# BT612-4.net
KiCad netlist of a schematic drawn in Altium Designer
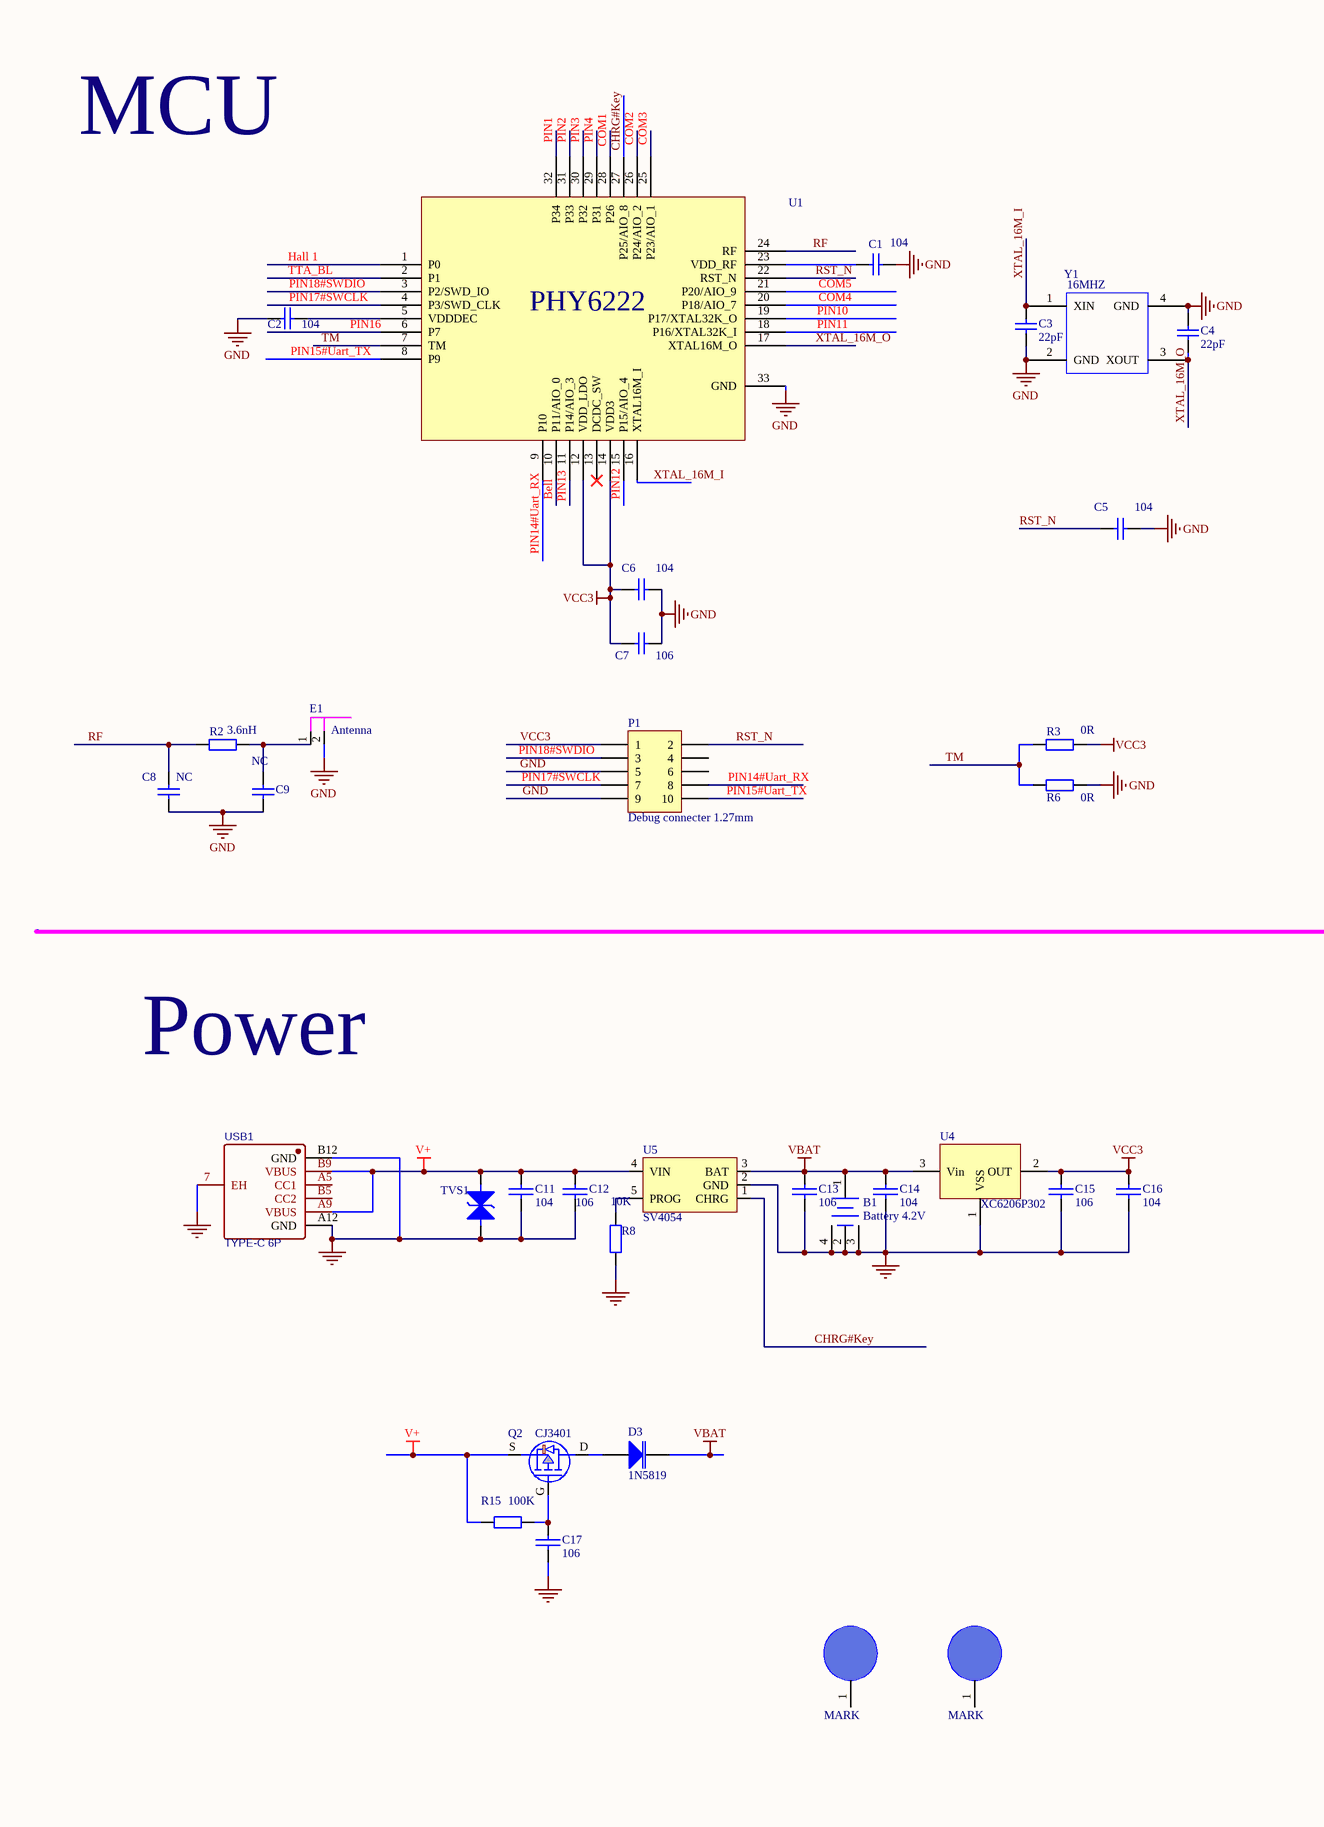
[diagram p0: BT612-4.SchDoc, left]
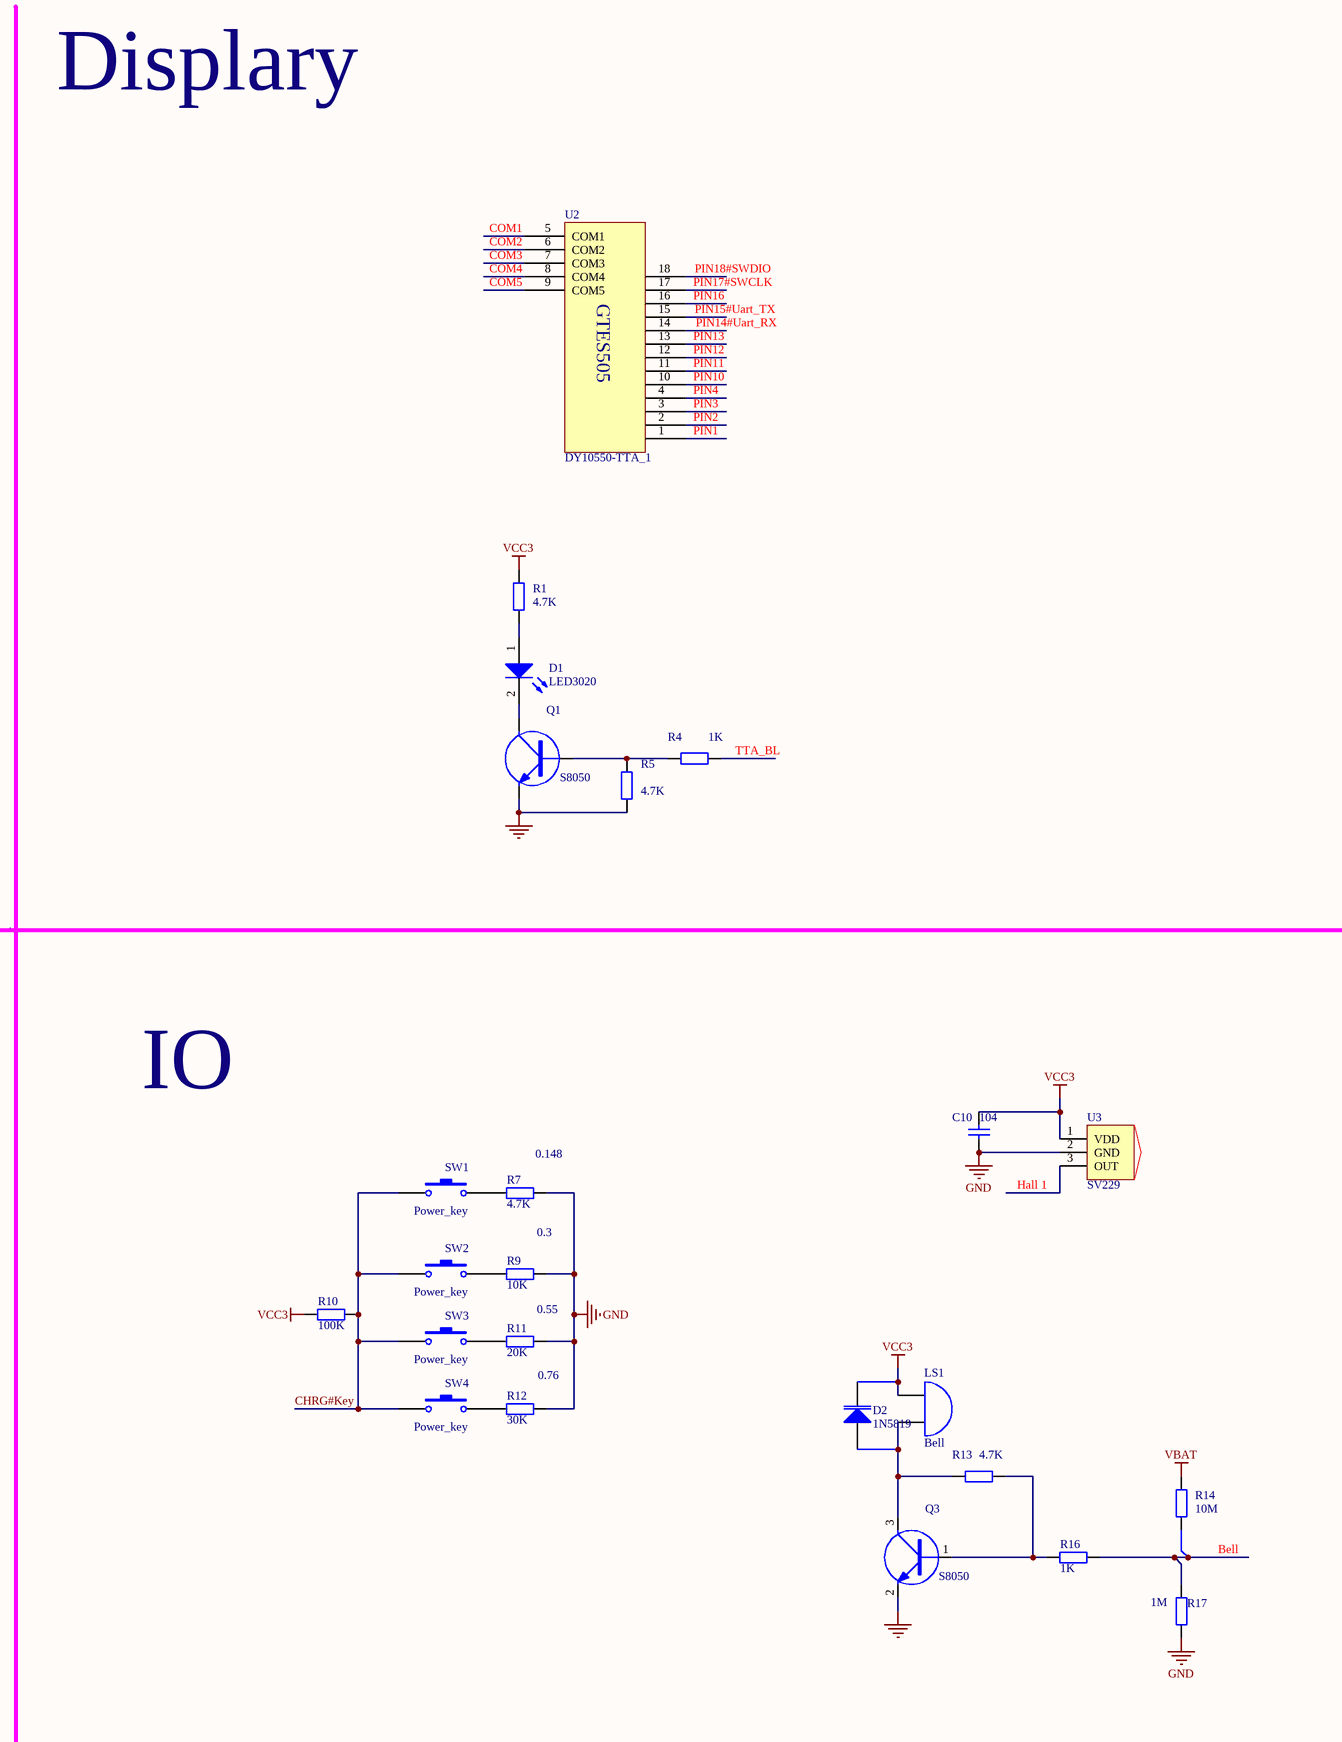
[diagram p1: BT612-4.SchDoc, right]

(export (version "E")
  (design (tool "Eeschema 10.0.6"))
  (components
    (comp (ref "B1")
      (value "Battery 4.2V")
      (footprint "BAT2P-1.25")
      (description "Multicell Battery")
      (fields (field (name "PUBLISHER") "Altium Limited"))
      (libsource (lib "SR4K_PHY6222_simplify_v1") (part "Battery"))
    )
    (comp (ref "C1")
      (value "104")
      (footprint "0402C")
      (description "Capacitor")
      (fields (field (name "PUBLISHER") "Altium Limited"))
      (libsource (lib "Miscellaneous Devices") (part "Cap"))
    )
    (comp (ref "C2")
      (value "104")
      (footprint "0402C")
      (description "Capacitor")
      (fields (field (name "PUBLISHER") "Altium Limited"))
      (libsource (lib "Miscellaneous Devices") (part "Cap"))
    )
    (comp (ref "C3")
      (value "22pF")
      (footprint "0402C")
      (description "Capacitor")
      (fields (field (name "PUBLISHER") "Altium Limited"))
      (libsource (lib "Miscellaneous Devices") (part "Cap"))
    )
    (comp (ref "C4")
      (value "22pF")
      (footprint "0402C")
      (description "Capacitor")
      (libsource (lib "Miscellaneous Devices") (part "Cap"))
    )
    (comp (ref "C5")
      (value "104")
      (footprint "0402C")
      (description "Capacitor")
      (fields (field (name "PUBLISHER") "Altium Limited"))
      (libsource (lib "Miscellaneous Devices") (part "Cap"))
    )
    (comp (ref "C6")
      (value "104")
      (footprint "0402C")
      (description "Capacitor")
      (fields (field (name "PUBLISHER") "Altium Limited"))
      (libsource (lib "Miscellaneous Devices") (part "Cap"))
    )
    (comp (ref "C7")
      (value "106")
      (footprint "0603-C")
      (description "Capacitor")
      (fields (field (name "PUBLISHER") "Altium Limited"))
      (libsource (lib "Miscellaneous Devices") (part "Cap"))
    )
    (comp (ref "C8")
      (value "NC")
      (footprint "0402C")
      (description "Capacitor")
      (fields (field (name "PUBLISHER") "Altium Limited"))
      (libsource (lib "Miscellaneous Devices") (part "Cap"))
    )
    (comp (ref "C9")
      (value "NC")
      (footprint "0402C")
      (description "Capacitor")
      (fields (field (name "PUBLISHER") "Altium Limited"))
      (libsource (lib "Miscellaneous Devices") (part "Cap"))
    )
    (comp (ref "C10")
      (value "104")
      (footprint "0402C")
      (description "Capacitor")
      (fields (field (name "PUBLISHER") "Altium Limited"))
      (libsource (lib "Miscellaneous Devices") (part "Cap"))
    )
    (comp (ref "C11")
      (value "104")
      (footprint "0402C")
      (description "Capacitor")
      (libsource (lib "*") (part "CAP"))
    )
    (comp (ref "C12")
      (value "106")
      (footprint "0603-C")
      (description "Capacitor")
      (libsource (lib "*") (part "CAP"))
    )
    (comp (ref "C13")
      (value "106")
      (footprint "0603-C")
      (description "Capacitor")
      (libsource (lib "*") (part "CAP"))
    )
    (comp (ref "C14")
      (value "104")
      (footprint "0402C")
      (description "Capacitor")
      (libsource (lib "*") (part "CAP"))
    )
    (comp (ref "C15")
      (value "106")
      (footprint "0603-C")
      (description "Capacitor")
      (libsource (lib "*") (part "CAP"))
    )
    (comp (ref "C16")
      (value "104")
      (footprint "0402C")
      (description "Capacitor")
      (libsource (lib "*") (part "CAP"))
    )
    (comp (ref "C17")
      (value "106")
      (footprint "0603-C")
      (description "Capacitor")
      (libsource (lib "*") (part "CAP"))
    )
    (comp (ref "D1")
      (value "LED3020")
      (footprint "LED-3020")
      (description "Typical INFRARED GaAs LED")
      (fields (field (name "PUBLISHER") "Altium Limited"))
      (libsource (lib "Miscellaneous Devices") (part "LED0"))
    )
    (comp (ref "D2")
      (value "1N5819")
      (footprint "SOD323")
      (description "Variable Capacitance Diode")
      (fields (field (name "PUBLISHER") "Altium Limited"))
      (libsource (lib "Miscellaneous Devices") (part "D Varactor"))
    )
    (comp (ref "D3")
      (value "1N5819")
      (footprint "SOD323")
      (description "Variable Capacitance Diode")
      (fields (field (name "PUBLISHER") "Altium Limited"))
      (libsource (lib "Miscellaneous Devices") (part "D Varactor"))
    )
    (comp (ref "E1") (value "Antenna") (footprint "BT-ANT") (libsource (lib "Schlib") (part "Antenna")))
    (comp (ref "LS1")
      (value "Bell")
      (footprint "BUZZ-12085")
      (description "Electrical Bell")
      (fields (field (name "PUBLISHER") "Altium Limited"))
      (libsource (lib "Miscellaneous Devices") (part "Bell"))
    )
    (comp (ref "P1")
      (value "Debug connecter 1.27mm")
      (footprint "SIP5-X2-1.27")
      (description "Header, 5-Pin, Dual row")
      (fields (field (name "PUBLISHER") "Altium Limited"))
      (libsource (lib "Miscellaneous Connectors") (part "Header 5X2"))
    )
    (comp (ref "Q1")
      (value "S8050")
      (footprint "SOT23")
      (description "NPN Transistor")
      (libsource (lib "*") (part "NPN"))
    )
    (comp (ref "Q2") (value "CJ3401") (footprint "SOT-23-GSD") (libsource (lib "*") (part "P-MOS")))
    (comp (ref "Q3")
      (value "S8050")
      (footprint "SOT23")
      (description "NPN Transistor")
      (libsource (lib "") (part "NPN_1"))
    )
    (comp (ref "R1")
      (value "4.7K")
      (footprint "0402R")
      (description "Resistor")
      (fields (field (name "PUBLISHER") "Altium Limited"))
      (libsource (lib "") (part "Res2_2"))
    )
    (comp (ref "R2")
      (value "3.6nH")
      (footprint "0402R")
      (description "Resistor")
      (fields (field (name "PUBLISHER") "Altium Limited"))
      (libsource (lib "") (part "Res2_1"))
    )
    (comp (ref "R3")
      (value "0R")
      (footprint "0402R")
      (description "Resistor")
      (fields (field (name "PUBLISHER") "Altium Limited"))
      (libsource (lib "") (part "Res2_1"))
    )
    (comp (ref "R4")
      (value "1K")
      (footprint "0402R")
      (description "Resistor")
      (fields (field (name "PUBLISHER") "Altium Limited"))
      (libsource (lib "Miscellaneous Devices") (part "Res2"))
    )
    (comp (ref "R5")
      (value "4.7K")
      (footprint "0402R")
      (description "Resistor")
      (fields (field (name "PUBLISHER") "Altium Limited"))
      (libsource (lib "") (part "Res2_2"))
    )
    (comp (ref "R6")
      (value "0R")
      (footprint "0402R")
      (description "Resistor")
      (fields (field (name "PUBLISHER") "Altium Limited"))
      (libsource (lib "") (part "Res2_1"))
    )
    (comp (ref "R7")
      (value "4.7K")
      (footprint "0402R")
      (description "Resistor")
      (fields (field (name "PUBLISHER") "Altium Limited"))
      (libsource (lib "Miscellaneous Devices") (part "Res2"))
    )
    (comp (ref "R8")
      (value "10K")
      (footprint "0402R")
      (description "1%@100mA")
      (fields (field (name "PUBLISHER") "Altium Limited"))
      (libsource (lib "") (part "Res2_2"))
    )
    (comp (ref "R9")
      (value "10K")
      (footprint "0402R")
      (description "Resistor")
      (fields (field (name "PUBLISHER") "Altium Limited"))
      (libsource (lib "Miscellaneous Devices") (part "Res2"))
    )
    (comp (ref "R10")
      (value "100K")
      (footprint "0402R")
      (description "Resistor")
      (fields (field (name "PUBLISHER") "Altium Limited"))
      (libsource (lib "Miscellaneous Devices") (part "Res2"))
    )
    (comp (ref "R11")
      (value "20K")
      (footprint "0402R")
      (description "Resistor")
      (fields (field (name "PUBLISHER") "Altium Limited"))
      (libsource (lib "Miscellaneous Devices") (part "Res2"))
    )
    (comp (ref "R12")
      (value "30K")
      (footprint "0402R")
      (description "Resistor")
      (fields (field (name "PUBLISHER") "Altium Limited"))
      (libsource (lib "Miscellaneous Devices") (part "Res2"))
    )
    (comp (ref "R13")
      (value "4.7K")
      (footprint "0402R")
      (description "Resistor")
      (fields (field (name "PUBLISHER") "Altium Limited"))
      (libsource (lib "") (part "Res2_1"))
    )
    (comp (ref "R14")
      (value "10M")
      (footprint "0402R")
      (description "Resistor")
      (fields (field (name "PUBLISHER") "Altium Limited"))
      (libsource (lib "") (part "Res2_2"))
    )
    (comp (ref "R15")
      (value "100K")
      (footprint "0402R")
      (description "1%@100mA")
      (fields (field (name "PUBLISHER") "Altium Limited"))
      (libsource (lib "") (part "Res2_1"))
    )
    (comp (ref "R16")
      (value "1K")
      (footprint "0402R")
      (description "Resistor")
      (fields (field (name "PUBLISHER") "Altium Limited"))
      (libsource (lib "Miscellaneous Devices") (part "Res2"))
    )
    (comp (ref "R17")
      (value "1M")
      (footprint "0402R")
      (description "Resistor")
      (fields (field (name "PUBLISHER") "Altium Limited"))
      (libsource (lib "") (part "Res2_2"))
    )
    (comp (ref "SW1")
      (value "Power_key")
      (footprint "SW_PB_SMD_4X4")
      (description "Switch")
      (fields (field (name "PUBLISHER") "Altium Limited"))
      (libsource (lib "Miscellaneous Devices") (part "SW-PB"))
    )
    (comp (ref "SW2")
      (value "Power_key")
      (footprint "SW_PB_SMD_4X4")
      (description "Switch")
      (fields (field (name "PUBLISHER") "Altium Limited"))
      (libsource (lib "Miscellaneous Devices") (part "SW-PB"))
    )
    (comp (ref "SW3")
      (value "Power_key")
      (footprint "SW_PB_SMD_4X4")
      (description "Switch")
      (fields (field (name "PUBLISHER") "Altium Limited"))
      (libsource (lib "Miscellaneous Devices") (part "SW-PB"))
    )
    (comp (ref "SW4")
      (value "Power_key")
      (footprint "SW_PB_SMD_4X4")
      (description "Switch")
      (fields (field (name "PUBLISHER") "Altium Limited"))
      (libsource (lib "Miscellaneous Devices") (part "SW-PB"))
    )
    (comp (ref "TP1") (value "MARK") (footprint "MARK") (libsource (lib "BT612-4") (part "TP")))
    (comp (ref "TP2") (value "MARK") (footprint "MARK") (libsource (lib "BT612-4") (part "TP")))
    (comp (ref "TVS1") (value "TVS") (footprint "SOD323") (libsource (lib "*") (part "TVS")))
    (comp (ref "U1")
      (value "PHY6222")
      (footprint "QFN32-4*4")
      (libsource (lib "SR4K_PHY6222_simplify_v1") (part "PHY6222"))
    )
    (comp (ref "U2")
      (value "DY10550-TTA_1")
      (footprint "GTES505液晶屏")
      (libsource (lib "BT612-4") (part "DY10550-TTA_1"))
    )
    (comp (ref "U3") (value "SV229") (footprint "SOT23-3") (libsource (lib "*") (part "霍尔44E 938")))
    (comp (ref "U4") (value "XC6206P302") (footprint "SOT23") (libsource (lib "*") (part "XC6206P302")))
    (comp (ref "U5") (value "SV4054") (footprint "SOT23-5") (libsource (lib "*") (part "SV4054")))
    (comp (ref "USB1")
      (value "TYPE-C 6P")
      (footprint "TYPE-C 6P")
      (fields (field (name "BOM_SUPPLIER PART") "C456012") (field (name "CONTRIBUTOR") "LCSC"))
      (libsource (lib "altium-import") (part "root_0_mirrored_TYPE-C 6P_"))
    )
    (comp (ref "Y1") (value "16MHZ") (footprint "JZ-3225") (libsource (lib "*") (part "X1_1")))
  )
  (nets
    (net (code "1") (name "/Bell") (class "Default")
      (node (ref "R14") (pin "1") (pinfunction "1_1") (pintype "passive"))
      (node (ref "R16") (pin "2") (pinfunction "2_2") (pintype "passive"))
      (node (ref "R17") (pin "2") (pinfunction "2_2") (pintype "passive"))
      (node (ref "U1") (pin "10") (pinfunction "P11/AIO_0_10") (pintype "passive"))
    )
    (net (code "2") (name "/CHRG#Key") (class "Default")
      (node (ref "R10") (pin "2") (pinfunction "2_2") (pintype "passive"))
      (node (ref "SW1") (pin "1") (pinfunction "1_1") (pintype "passive"))
      (node (ref "SW2") (pin "1") (pinfunction "1_1") (pintype "passive"))
      (node (ref "SW3") (pin "1") (pinfunction "1_1") (pintype "passive"))
      (node (ref "SW4") (pin "1") (pinfunction "1_1") (pintype "passive"))
      (node (ref "U1") (pin "27") (pinfunction "P25/AIO_8_27") (pintype "passive"))
      (node (ref "U5") (pin "1") (pinfunction "CHRG_1") (pintype "passive"))
    )
    (net (code "3") (name "/COM1") (class "Default")
      (node (ref "U1") (pin "28") (pinfunction "P26_28") (pintype "passive"))
      (node (ref "U2") (pin "5") (pinfunction "COM1_5") (pintype "passive"))
    )
    (net (code "4") (name "/COM2") (class "Default")
      (node (ref "U1") (pin "26") (pinfunction "P24/AIO_2_26") (pintype "passive"))
      (node (ref "U2") (pin "6") (pinfunction "COM2_6") (pintype "passive"))
    )
    (net (code "5") (name "/COM3") (class "Default")
      (node (ref "U1") (pin "25") (pinfunction "P23/AIO_1_25") (pintype "passive"))
      (node (ref "U2") (pin "7") (pinfunction "COM3_7") (pintype "passive"))
    )
    (net (code "6") (name "/COM4") (class "Default")
      (node (ref "U1") (pin "20") (pinfunction "P18/AIO_7_20") (pintype "passive"))
      (node (ref "U2") (pin "8") (pinfunction "COM4_8") (pintype "passive"))
    )
    (net (code "7") (name "/COM5") (class "Default")
      (node (ref "U1") (pin "21") (pinfunction "P20/AIO_9_21") (pintype "passive"))
      (node (ref "U2") (pin "9") (pinfunction "COM5_9") (pintype "passive"))
    )
    (net (code "8") (name "/Hall 1") (class "Default")
      (node (ref "U1") (pin "1") (pinfunction "P0_1") (pintype "passive"))
      (node (ref "U3") (pin "3") (pinfunction "OUT_3") (pintype "passive"))
    )
    (net (code "9") (name "/PIN1") (class "Default")
      (node (ref "U1") (pin "32") (pinfunction "P34_32") (pintype "passive"))
      (node (ref "U2") (pin "1") (pintype "passive"))
    )
    (net (code "10") (name "/PIN2") (class "Default")
      (node (ref "U1") (pin "31") (pinfunction "P33_31") (pintype "passive"))
      (node (ref "U2") (pin "2") (pintype "passive"))
    )
    (net (code "11") (name "/PIN3") (class "Default")
      (node (ref "U1") (pin "30") (pinfunction "P32_30") (pintype "passive"))
      (node (ref "U2") (pin "3") (pintype "passive"))
    )
    (net (code "12") (name "/PIN4") (class "Default")
      (node (ref "U1") (pin "29") (pinfunction "P31_29") (pintype "passive"))
      (node (ref "U2") (pin "4") (pintype "passive"))
    )
    (net (code "13") (name "/PIN10") (class "Default")
      (node (ref "U1") (pin "19") (pinfunction "P17/XTAL32K_O_19") (pintype "passive"))
      (node (ref "U2") (pin "10") (pintype "passive"))
    )
    (net (code "14") (name "/PIN11") (class "Default")
      (node (ref "U1") (pin "18") (pinfunction "P16/XTAL32K_I_18") (pintype "passive"))
      (node (ref "U2") (pin "11") (pintype "passive"))
    )
    (net (code "15") (name "/PIN12") (class "Default")
      (node (ref "U1") (pin "15") (pinfunction "P15/AIO_4_15") (pintype "passive"))
      (node (ref "U2") (pin "12") (pintype "passive"))
    )
    (net (code "16") (name "/PIN13") (class "Default")
      (node (ref "U1") (pin "11") (pinfunction "P14/AIO_3_11") (pintype "passive"))
      (node (ref "U2") (pin "13") (pintype "passive"))
    )
    (net (code "17") (name "/PIN14#Uart_RX") (class "Default")
      (node (ref "P1") (pin "8") (pinfunction "8_8") (pintype "passive"))
      (node (ref "U1") (pin "9") (pinfunction "P10_9") (pintype "passive"))
      (node (ref "U2") (pin "14") (pintype "passive"))
    )
    (net (code "18") (name "/PIN15#Uart_TX") (class "Default")
      (node (ref "P1") (pin "10") (pinfunction "10_10") (pintype "passive"))
      (node (ref "U1") (pin "8") (pinfunction "P9_8") (pintype "passive"))
      (node (ref "U2") (pin "15") (pintype "passive"))
    )
    (net (code "19") (name "/PIN16") (class "Default")
      (node (ref "U1") (pin "6") (pinfunction "P7_6") (pintype "passive"))
      (node (ref "U2") (pin "16") (pintype "passive"))
    )
    (net (code "20") (name "/PIN17#SWCLK") (class "Default")
      (node (ref "P1") (pin "7") (pinfunction "7_7") (pintype "passive"))
      (node (ref "U1") (pin "4") (pinfunction "P3/SWD_CLK_4") (pintype "passive"))
      (node (ref "U2") (pin "17") (pintype "passive"))
    )
    (net (code "21") (name "/PIN18#SWDIO") (class "Default")
      (node (ref "P1") (pin "3") (pinfunction "3_3") (pintype "passive"))
      (node (ref "U1") (pin "3") (pinfunction "P2/SWD_IO_3") (pintype "passive"))
      (node (ref "U2") (pin "18") (pintype "passive"))
    )
    (net (code "22") (name "/RF") (class "Default")
      (node (ref "C8") (pin "1") (pinfunction "1_1") (pintype "passive"))
      (node (ref "R2") (pin "2") (pinfunction "2_2") (pintype "passive"))
      (node (ref "U1") (pin "24") (pinfunction "RF_24") (pintype "passive"))
    )
    (net (code "23") (name "/RST_N") (class "Default")
      (node (ref "C5") (pin "1") (pinfunction "1_1") (pintype "passive"))
      (node (ref "P1") (pin "2") (pinfunction "2_2") (pintype "passive"))
      (node (ref "U1") (pin "22") (pinfunction "RST_N_22") (pintype "passive"))
    )
    (net (code "24") (name "/TM") (class "Default")
      (node (ref "R3") (pin "2") (pinfunction "2_2") (pintype "passive"))
      (node (ref "R6") (pin "2") (pinfunction "2_2") (pintype "passive"))
      (node (ref "U1") (pin "7") (pinfunction "TM_7") (pintype "passive"))
    )
    (net (code "25") (name "/TTA_BL") (class "Default")
      (node (ref "R4") (pin "2") (pinfunction "2_2") (pintype "passive"))
      (node (ref "U1") (pin "2") (pinfunction "P1_2") (pintype "passive"))
    )
    (net (code "26") (name "/XTAL_16M_I") (class "Default")
      (node (ref "C3") (pin "1") (pinfunction "1_1") (pintype "passive"))
      (node (ref "U1") (pin "16") (pinfunction "XTAL16M_I_16") (pintype "passive"))
      (node (ref "Y1") (pin "1") (pinfunction "XIN_1") (pintype "passive"))
    )
    (net (code "27") (name "/XTAL_16M_O") (class "Default")
      (node (ref "C4") (pin "2") (pinfunction "2_2") (pintype "passive"))
      (node (ref "U1") (pin "17") (pinfunction "XTAL16M_O_17") (pintype "passive"))
      (node (ref "Y1") (pin "3") (pinfunction "XOUT_3") (pintype "passive"))
    )
    (net (code "28") (name "GND") (class "Default")
      (node (ref "B1") (pin "2") (pinfunction "-_2") (pintype "passive"))
      (node (ref "B1") (pin "3") (pinfunction "3_3") (pintype "passive"))
      (node (ref "B1") (pin "4") (pinfunction "4_4") (pintype "passive"))
      (node (ref "C1") (pin "2") (pinfunction "2_2") (pintype "passive"))
      (node (ref "C10") (pin "2") (pinfunction "2_2") (pintype "passive"))
      (node (ref "C11") (pin "1") (pinfunction "1_1") (pintype "passive"))
      (node (ref "C12") (pin "1") (pinfunction "1_1") (pintype "passive"))
      (node (ref "C13") (pin "1") (pinfunction "1_1") (pintype "passive"))
      (node (ref "C14") (pin "1") (pinfunction "1_1") (pintype "passive"))
      (node (ref "C15") (pin "1") (pinfunction "1_1") (pintype "passive"))
      (node (ref "C16") (pin "1") (pinfunction "1_1") (pintype "passive"))
      (node (ref "C17") (pin "1") (pinfunction "1_1") (pintype "passive"))
      (node (ref "C2") (pin "1") (pinfunction "1_1") (pintype "passive"))
      (node (ref "C3") (pin "2") (pinfunction "2_2") (pintype "passive"))
      (node (ref "C4") (pin "1") (pinfunction "1_1") (pintype "passive"))
      (node (ref "C5") (pin "2") (pinfunction "2_2") (pintype "passive"))
      (node (ref "C6") (pin "2") (pinfunction "2_2") (pintype "passive"))
      (node (ref "C7") (pin "2") (pinfunction "2_2") (pintype "passive"))
      (node (ref "C8") (pin "2") (pinfunction "2_2") (pintype "passive"))
      (node (ref "C9") (pin "2") (pinfunction "2_2") (pintype "passive"))
      (node (ref "E1") (pin "2") (pinfunction "2_2") (pintype "passive"))
      (node (ref "P1") (pin "5") (pinfunction "5_5") (pintype "passive"))
      (node (ref "P1") (pin "9") (pinfunction "9_9") (pintype "passive"))
      (node (ref "Q1") (pin "2") (pinfunction "E_2") (pintype "passive"))
      (node (ref "Q3") (pin "2") (pinfunction "E_2") (pintype "passive"))
      (node (ref "R11") (pin "2") (pinfunction "2_2") (pintype "passive"))
      (node (ref "R12") (pin "2") (pinfunction "2_2") (pintype "passive"))
      (node (ref "R17") (pin "1") (pinfunction "1_1") (pintype "passive"))
      (node (ref "R5") (pin "1") (pinfunction "1_1") (pintype "passive"))
      (node (ref "R6") (pin "1") (pinfunction "1_1") (pintype "passive"))
      (node (ref "R7") (pin "2") (pinfunction "2_2") (pintype "passive"))
      (node (ref "R8") (pin "1") (pinfunction "1_1") (pintype "passive"))
      (node (ref "R9") (pin "2") (pinfunction "2_2") (pintype "passive"))
      (node (ref "TVS1") (pin "1") (pinfunction "1_1") (pintype "passive"))
      (node (ref "U1") (pin "33") (pinfunction "GND_33") (pintype "power_in"))
      (node (ref "U3") (pin "2") (pinfunction "GND_2") (pintype "passive"))
      (node (ref "U4") (pin "1") (pinfunction "VSS_1") (pintype "passive"))
      (node (ref "U5") (pin "2") (pinfunction "GND_2") (pintype "passive"))
      (node (ref "USB1") (pin "7") (pinfunction "EH_7") (pintype "passive"))
      (node (ref "USB1") (pin "A12") (pinfunction "GND_A12") (pintype "passive"))
      (node (ref "USB1") (pin "B12") (pinfunction "GND_B12") (pintype "passive"))
      (node (ref "Y1") (pin "2") (pinfunction "GND_2") (pintype "power_in"))
      (node (ref "Y1") (pin "4") (pinfunction "GND_4") (pintype "power_in"))
    )
    (net (code "29") (name "Net-(C9-Pad1)") (class "Default")
      (node (ref "C9") (pin "1") (pinfunction "1_1") (pintype "passive"))
      (node (ref "E1") (pin "1") (pinfunction "1_1") (pintype "passive"))
      (node (ref "R2") (pin "1") (pinfunction "1_1") (pintype "passive"))
    )
    (net (code "30") (name "Net-(D1-A)") (class "Default")
      (node (ref "D1") (pin "1") (pinfunction "A_1") (pintype "passive"))
      (node (ref "R1") (pin "1") (pinfunction "1_1") (pintype "passive"))
    )
    (net (code "31") (name "Net-(D1-K)") (class "Default")
      (node (ref "D1") (pin "2") (pinfunction "K_2") (pintype "passive"))
      (node (ref "Q1") (pin "3") (pinfunction "C_3") (pintype "passive"))
    )
    (net (code "32") (name "Net-(LS1-B)") (class "Default")
      (node (ref "D2") (pin "1") (pinfunction "1_1") (pintype "passive"))
      (node (ref "LS1") (pin "2") (pinfunction "B_2") (pintype "passive"))
      (node (ref "Q3") (pin "3") (pinfunction "C_3") (pintype "passive"))
      (node (ref "R13") (pin "2") (pinfunction "2_2") (pintype "passive"))
    )
    (net (code "33") (name "Net-(Q1-B)") (class "Default")
      (node (ref "Q1") (pin "1") (pinfunction "B_1") (pintype "passive"))
      (node (ref "R4") (pin "1") (pinfunction "1_1") (pintype "passive"))
      (node (ref "R5") (pin "2") (pinfunction "2_2") (pintype "passive"))
    )
    (net (code "34") (name "Net-(Q2-DRAIN)") (class "Default")
      (node (ref "D3") (pin "1") (pinfunction "1_1") (pintype "passive"))
      (node (ref "Q2") (pin "D") (pinfunction "DRAIN_D") (pintype "passive"))
    )
    (net (code "35") (name "Net-(Q2-GATE)") (class "Default")
      (node (ref "C17") (pin "2") (pinfunction "2_2") (pintype "passive"))
      (node (ref "Q2") (pin "G") (pinfunction "GATE_G") (pintype "passive"))
      (node (ref "R15") (pin "1") (pinfunction "1_1") (pintype "passive"))
    )
    (net (code "36") (name "Net-(Q3-B)") (class "Default")
      (node (ref "Q3") (pin "1") (pinfunction "B_1") (pintype "passive"))
      (node (ref "R13") (pin "1") (pinfunction "1_1") (pintype "passive"))
      (node (ref "R16") (pin "1") (pinfunction "1_1") (pintype "passive"))
    )
    (net (code "37") (name "Net-(R7-Pad1)") (class "Default")
      (node (ref "R7") (pin "1") (pinfunction "1_1") (pintype "passive"))
      (node (ref "SW1") (pin "2") (pinfunction "2_2") (pintype "passive"))
    )
    (net (code "38") (name "Net-(R9-Pad1)") (class "Default")
      (node (ref "R9") (pin "1") (pinfunction "1_1") (pintype "passive"))
      (node (ref "SW2") (pin "2") (pinfunction "2_2") (pintype "passive"))
    )
    (net (code "39") (name "Net-(R11-Pad1)") (class "Default")
      (node (ref "R11") (pin "1") (pinfunction "1_1") (pintype "passive"))
      (node (ref "SW3") (pin "2") (pinfunction "2_2") (pintype "passive"))
    )
    (net (code "40") (name "Net-(R12-Pad1)") (class "Default")
      (node (ref "R12") (pin "1") (pinfunction "1_1") (pintype "passive"))
      (node (ref "SW4") (pin "2") (pinfunction "2_2") (pintype "passive"))
    )
    (net (code "41") (name "Net-(U1-VDDDEC)") (class "Default")
      (node (ref "C2") (pin "2") (pinfunction "2_2") (pintype "passive"))
      (node (ref "U1") (pin "5") (pinfunction "VDDDEC_5") (pintype "power_in"))
    )
    (net (code "42") (name "Net-(U1-VDD_RF)") (class "Default")
      (node (ref "C1") (pin "1") (pinfunction "1_1") (pintype "passive"))
      (node (ref "U1") (pin "23") (pinfunction "VDD_RF_23") (pintype "power_in"))
    )
    (net (code "43") (name "Net-(U5-PROG)") (class "Default")
      (node (ref "R8") (pin "2") (pinfunction "2_2") (pintype "passive"))
      (node (ref "U5") (pin "5") (pinfunction "PROG_5") (pintype "passive"))
    )
    (net (code "44") (name "V+") (class "Default")
      (node (ref "C11") (pin "2") (pinfunction "2_2") (pintype "passive"))
      (node (ref "C12") (pin "2") (pinfunction "2_2") (pintype "passive"))
      (node (ref "Q2") (pin "S") (pinfunction "SOURCE_S") (pintype "passive"))
      (node (ref "R15") (pin "2") (pinfunction "2_2") (pintype "passive"))
      (node (ref "TVS1") (pin "2") (pinfunction "2_2") (pintype "passive"))
      (node (ref "U5") (pin "4") (pinfunction "VIN_4") (pintype "passive"))
      (node (ref "USB1") (pin "A9") (pinfunction "VBUS_A9") (pintype "passive"))
      (node (ref "USB1") (pin "B9") (pinfunction "VBUS_B9") (pintype "passive"))
    )
    (net (code "45") (name "VBAT") (class "Default")
      (node (ref "B1") (pin "1") (pinfunction "+_1") (pintype "passive"))
      (node (ref "C13") (pin "2") (pinfunction "2_2") (pintype "passive"))
      (node (ref "C14") (pin "2") (pinfunction "2_2") (pintype "passive"))
      (node (ref "D3") (pin "2") (pinfunction "2_2") (pintype "passive"))
      (node (ref "R14") (pin "2") (pinfunction "2_2") (pintype "passive"))
      (node (ref "U4") (pin "3") (pinfunction "Vin_3") (pintype "passive"))
      (node (ref "U5") (pin "3") (pinfunction "BAT_3") (pintype "passive"))
    )
    (net (code "46") (name "VCC3") (class "Default")
      (node (ref "C10") (pin "1") (pinfunction "1_1") (pintype "passive"))
      (node (ref "C15") (pin "2") (pinfunction "2_2") (pintype "passive"))
      (node (ref "C16") (pin "2") (pinfunction "2_2") (pintype "passive"))
      (node (ref "C6") (pin "1") (pinfunction "1_1") (pintype "passive"))
      (node (ref "C7") (pin "1") (pinfunction "1_1") (pintype "passive"))
      (node (ref "D2") (pin "2") (pinfunction "2_2") (pintype "passive"))
      (node (ref "LS1") (pin "1") (pinfunction "A_1") (pintype "passive"))
      (node (ref "P1") (pin "1") (pinfunction "1_1") (pintype "passive"))
      (node (ref "R1") (pin "2") (pinfunction "2_2") (pintype "passive"))
      (node (ref "R10") (pin "1") (pinfunction "1_1") (pintype "passive"))
      (node (ref "R3") (pin "1") (pinfunction "1_1") (pintype "passive"))
      (node (ref "U1") (pin "12") (pinfunction "VDD_LDO_12") (pintype "power_in"))
      (node (ref "U1") (pin "14") (pinfunction "VDD3_14") (pintype "power_in"))
      (node (ref "U3") (pin "1") (pinfunction "VDD_1") (pintype "passive"))
      (node (ref "U4") (pin "2") (pinfunction "OUT_2") (pintype "passive"))
    )
    (net (code "47") (name "unconnected-(P1-Pad4)") (class "Default")
      (node (ref "P1") (pin "4") (pinfunction "4_4") (pintype "passive"))
    )
    (net (code "48") (name "unconnected-(P1-Pad6)") (class "Default")
      (node (ref "P1") (pin "6") (pinfunction "6_6") (pintype "passive"))
    )
    (net (code "49") (name "unconnected-(TP1-Pad1)") (class "Default")
      (node (ref "TP1") (pin "1") (pinfunction "1_1") (pintype "passive"))
    )
    (net (code "50") (name "unconnected-(TP2-Pad1)") (class "Default")
      (node (ref "TP2") (pin "1") (pinfunction "1_1") (pintype "passive"))
    )
    (net (code "51") (name "unconnected-(U1-DCDC_SW-Pad13)") (class "Default")
      (node (ref "U1") (pin "13") (pinfunction "DCDC_SW_13") (pintype "power_in+no_connect"))
    )
    (net (code "52") (name "unconnected-(USB1-CC1-PadA5)") (class "Default")
      (node (ref "USB1") (pin "A5") (pinfunction "CC1_A5") (pintype "passive"))
    )
    (net (code "53") (name "unconnected-(USB1-CC2-PadB5)") (class "Default")
      (node (ref "USB1") (pin "B5") (pinfunction "CC2_B5") (pintype "passive"))
    )
  )
)
